# Power.net
KiCad netlist of a schematic drawn in Altium Designer
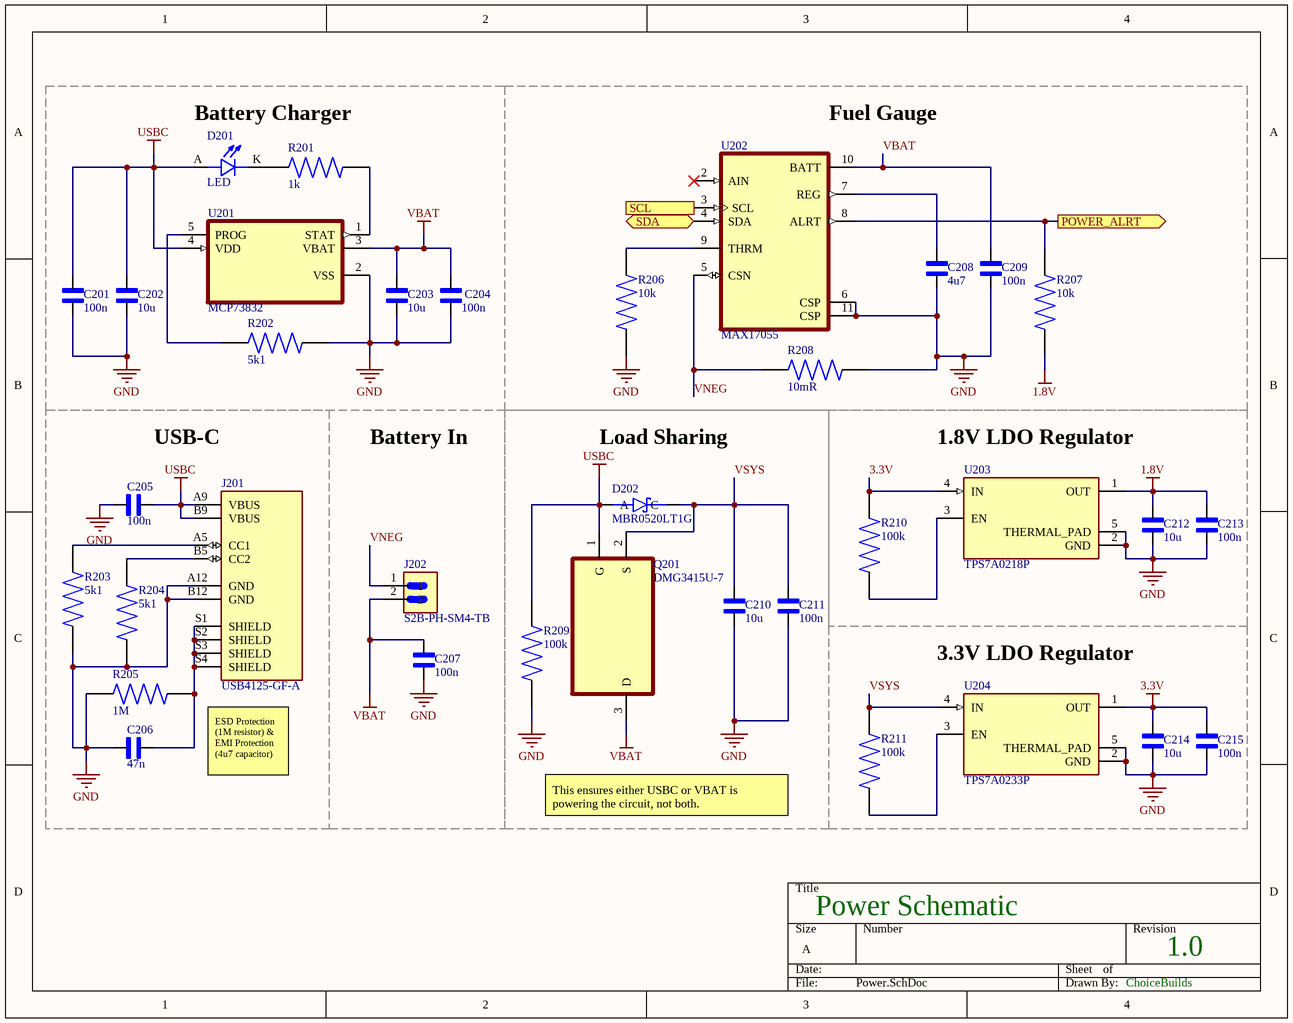
[diagram p0: Power.SchDoc]

(export (version "E")
  (design (tool "Eeschema 10.0.6"))
  (components
    (comp (ref "C201") (value "100n") (footprint "0402c") (libsource (lib "") (part "0402c_1")))
    (comp (ref "C202") (value "10u") (footprint "0603c") (libsource (lib "UbiWatch_SchLib") (part "0603c")))
    (comp (ref "C203") (value "10u") (footprint "0603c") (libsource (lib "") (part "0603c_1")))
    (comp (ref "C204") (value "100n") (footprint "0402c") (libsource (lib "") (part "0402c_1")))
    (comp (ref "C205") (value "100n") (footprint "0402c") (libsource (lib "") (part "0402c_2")))
    (comp (ref "C206") (value "47n") (footprint "0402c") (libsource (lib "") (part "0402c_2")))
    (comp (ref "C207") (value "100n") (footprint "0402c") (libsource (lib "UbiWatch_SchLib") (part "0402c")))
    (comp (ref "C208") (value "4u7") (footprint "0603c") (libsource (lib "UbiWatch_SchLib") (part "0603c")))
    (comp (ref "C209") (value "100n") (footprint "0402c") (libsource (lib "") (part "0402c_1")))
    (comp (ref "C210") (value "10u") (footprint "0603c") (libsource (lib "UbiWatch_SchLib") (part "0603c")))
    (comp (ref "C211") (value "100n") (footprint "0402c") (libsource (lib "") (part "0402c_1")))
    (comp (ref "C212") (value "10u") (footprint "0603c") (libsource (lib "UbiWatch_SchLib") (part "0603c")))
    (comp (ref "C213") (value "100n") (footprint "0402c") (libsource (lib "") (part "0402c_1")))
    (comp (ref "C214") (value "10u") (footprint "0603c") (libsource (lib "UbiWatch_SchLib") (part "0603c")))
    (comp (ref "C215") (value "100n") (footprint "0402c") (libsource (lib "") (part "0402c_1")))
    (comp (ref "D201") (value "LED") (footprint ".LED") (libsource (lib "UbiWatch_SchLib") (part ".LED")))
    (comp (ref "D202")
      (value "MBR0520LT1G")
      (footprint "MBR0520LT1G")
      (libsource (lib "UbiWatch_SchLib") (part "MBR0520LT1G"))
    )
    (comp (ref "J201")
      (value "USB4125-GF-A")
      (footprint "USB4125-GF-A")
      (libsource (lib "JWatch_SchLib") (part "USB4125-GF-A"))
    )
    (comp (ref "J202")
      (value "S2B-PH-SM4-TB")
      (footprint "S2B-PH-SM4-TB")
      (libsource (lib "UbiWatch_SchLib") (part "S2B-PH-SM4-TB"))
    )
    (comp (ref "Q201")
      (value "DMG3415U-7")
      (footprint "DMG3415U-7")
      (libsource (lib "UbiWatch_SchLib") (part "DMG3415U-7"))
    )
    (comp (ref "R201") (value "1k") (footprint "0402r") (libsource (lib "UbiWatch_SchLib") (part "0402r")))
    (comp (ref "R202") (value "5k1") (footprint "0402r") (libsource (lib "UbiWatch_SchLib") (part "0402r")))
    (comp (ref "R203") (value "5k1") (footprint "0402r") (libsource (lib "UbiWatch_SchLib") (part "0402r")))
    (comp (ref "R204") (value "5k1") (footprint "0402r") (libsource (lib "UbiWatch_SchLib") (part "0402r")))
    (comp (ref "R205") (value "1M") (footprint "0402r") (libsource (lib "UbiWatch_SchLib") (part "0402r")))
    (comp (ref "R206") (value "10k") (footprint "0402r") (libsource (lib "UbiWatch_SchLib") (part "0402r")))
    (comp (ref "R207") (value "10k") (footprint "0402r") (libsource (lib "UbiWatch_SchLib") (part "0402r")))
    (comp (ref "R208") (value "10mR") (footprint "0805r") (libsource (lib "UbiWatch_SchLib") (part "0805r")))
    (comp (ref "R209") (value "100k") (footprint "0402r") (libsource (lib "UbiWatch_SchLib") (part "0402r")))
    (comp (ref "R210") (value "100k") (footprint "0402r") (libsource (lib "UbiWatch_SchLib") (part "0402r")))
    (comp (ref "R211") (value "100k") (footprint "0402r") (libsource (lib "UbiWatch_SchLib") (part "0402r")))
    (comp (ref "U201")
      (value "MCP73832")
      (footprint "MCP73832")
      (libsource (lib "JWatch_SchLib") (part "MCP73832"))
    )
    (comp (ref "U202")
      (value "MAX17055")
      (footprint "MAX17055")
      (libsource (lib "JWatch_SchLib") (part "MAX17055"))
    )
    (comp (ref "U203")
      (value "TPS7A0218P")
      (footprint "TPS7A0218P")
      (libsource (lib "JWatch_SchLib") (part "TPS7A0218P"))
    )
    (comp (ref "U204")
      (value "TPS7A0233P")
      (footprint "TPS7A0233P")
      (libsource (lib "JWatch_SchLib") (part "TPS7A0233P"))
    )
  )
  (nets
    (net (code "1") (name "/POWER_ALRT") (class "Default")
      (node (ref "R207") (pin "2") (pinfunction "2_2") (pintype "passive"))
      (node (ref "U202") (pin "8") (pinfunction "ALRT_8") (pintype "output"))
    )
    (net (code "2") (name "/SCL") (class "Default")
      (node (ref "U202") (pin "3") (pinfunction "SCL_3") (pintype "input"))
    )
    (net (code "3") (name "/SDA") (class "Default")
      (node (ref "U202") (pin "4") (pinfunction "SDA_4") (pintype "input"))
    )
    (net (code "4") (name "/VNEG") (class "Default")
      (node (ref "J202") (pin "1") (pinfunction "1_1") (pintype "passive"))
      (node (ref "R208") (pin "1") (pinfunction "1_1") (pintype "passive"))
      (node (ref "U202") (pin "5") (pinfunction "CSN_5") (pintype "bidirectional"))
    )
    (net (code "5") (name "/VSYS") (class "Default")
      (node (ref "C210") (pin "2") (pinfunction "2_2") (pintype "passive"))
      (node (ref "C211") (pin "2") (pinfunction "2_2") (pintype "passive"))
      (node (ref "D202") (pin "C") (pinfunction "C_C") (pintype "passive"))
      (node (ref "Q201") (pin "2") (pinfunction "S_2") (pintype "power_in"))
      (node (ref "R211") (pin "2") (pinfunction "2_2") (pintype "passive"))
      (node (ref "U204") (pin "4") (pinfunction "IN_4") (pintype "input"))
    )
    (net (code "6") (name "1.8V") (class "Default")
      (node (ref "C212") (pin "2") (pinfunction "2_2") (pintype "passive"))
      (node (ref "C213") (pin "2") (pinfunction "2_2") (pintype "passive"))
      (node (ref "R207") (pin "1") (pinfunction "1_1") (pintype "passive"))
      (node (ref "U203") (pin "1") (pinfunction "OUT_1") (pintype "power_in"))
    )
    (net (code "7") (name "3.3V") (class "Default")
      (node (ref "C214") (pin "2") (pinfunction "2_2") (pintype "passive"))
      (node (ref "C215") (pin "2") (pinfunction "2_2") (pintype "passive"))
      (node (ref "R210") (pin "2") (pinfunction "2_2") (pintype "passive"))
      (node (ref "U203") (pin "4") (pinfunction "IN_4") (pintype "input"))
      (node (ref "U204") (pin "1") (pinfunction "OUT_1") (pintype "power_in"))
    )
    (net (code "8") (name "GND") (class "Default")
      (node (ref "C201") (pin "1") (pinfunction "1_1") (pintype "passive"))
      (node (ref "C202") (pin "1") (pinfunction "1_1") (pintype "passive"))
      (node (ref "C203") (pin "1") (pinfunction "1_1") (pintype "passive"))
      (node (ref "C204") (pin "1") (pinfunction "1_1") (pintype "passive"))
      (node (ref "C205") (pin "1") (pinfunction "1_1") (pintype "passive"))
      (node (ref "C206") (pin "1") (pinfunction "1_1") (pintype "passive"))
      (node (ref "C207") (pin "2") (pinfunction "2_2") (pintype "passive"))
      (node (ref "C208") (pin "1") (pinfunction "1_1") (pintype "passive"))
      (node (ref "C209") (pin "1") (pinfunction "1_1") (pintype "passive"))
      (node (ref "C210") (pin "1") (pinfunction "1_1") (pintype "passive"))
      (node (ref "C211") (pin "1") (pinfunction "1_1") (pintype "passive"))
      (node (ref "C212") (pin "1") (pinfunction "1_1") (pintype "passive"))
      (node (ref "C213") (pin "1") (pinfunction "1_1") (pintype "passive"))
      (node (ref "C214") (pin "1") (pinfunction "1_1") (pintype "passive"))
      (node (ref "C215") (pin "1") (pinfunction "1_1") (pintype "passive"))
      (node (ref "J201") (pin "A12") (pinfunction "GND_A12") (pintype "power_in"))
      (node (ref "J201") (pin "B12") (pinfunction "GND_B12") (pintype "power_in"))
      (node (ref "R202") (pin "2") (pinfunction "2_2") (pintype "passive"))
      (node (ref "R203") (pin "1") (pinfunction "1_1") (pintype "passive"))
      (node (ref "R204") (pin "1") (pinfunction "1_1") (pintype "passive"))
      (node (ref "R205") (pin "1") (pinfunction "1_1") (pintype "passive"))
      (node (ref "R206") (pin "1") (pinfunction "1_1") (pintype "passive"))
      (node (ref "R208") (pin "2") (pinfunction "2_2") (pintype "passive"))
      (node (ref "R209") (pin "1") (pinfunction "1_1") (pintype "passive"))
      (node (ref "U201") (pin "2") (pinfunction "VSS_2") (pintype "power_in"))
      (node (ref "U202") (pin "11") (pinfunction "CSP_11") (pintype "power_in"))
      (node (ref "U202") (pin "6") (pinfunction "CSP_6") (pintype "power_in"))
      (node (ref "U203") (pin "2") (pinfunction "GND_2") (pintype "power_in"))
      (node (ref "U203") (pin "5") (pinfunction "THERMAL_PAD_5") (pintype "power_in"))
      (node (ref "U204") (pin "2") (pinfunction "GND_2") (pintype "power_in"))
      (node (ref "U204") (pin "5") (pinfunction "THERMAL_PAD_5") (pintype "power_in"))
    )
    (net (code "9") (name "Net-(C206-Pad2)") (class "Default")
      (node (ref "C206") (pin "2") (pinfunction "2_2") (pintype "passive"))
      (node (ref "J201") (pin "S1") (pinfunction "SHIELD_S1") (pintype "passive"))
      (node (ref "J201") (pin "S2") (pinfunction "SHIELD_S2") (pintype "passive"))
      (node (ref "J201") (pin "S3") (pinfunction "SHIELD_S3") (pintype "passive"))
      (node (ref "J201") (pin "S4") (pinfunction "SHIELD_S4") (pintype "passive"))
      (node (ref "R205") (pin "2") (pinfunction "2_2") (pintype "passive"))
    )
    (net (code "10") (name "Net-(D201-PadK)") (class "Default")
      (node (ref "D201") (pin "K") (pinfunction "K_K") (pintype "passive"))
      (node (ref "R201") (pin "1") (pinfunction "1_1") (pintype "passive"))
    )
    (net (code "11") (name "Net-(J201-CC1)") (class "Default")
      (node (ref "J201") (pin "A5") (pinfunction "CC1_A5") (pintype "bidirectional"))
      (node (ref "R203") (pin "2") (pinfunction "2_2") (pintype "passive"))
    )
    (net (code "12") (name "Net-(J201-CC2)") (class "Default")
      (node (ref "J201") (pin "B5") (pinfunction "CC2_B5") (pintype "bidirectional"))
      (node (ref "R204") (pin "2") (pinfunction "2_2") (pintype "passive"))
    )
    (net (code "13") (name "Net-(U201-PROG)") (class "Default")
      (node (ref "R202") (pin "1") (pinfunction "1_1") (pintype "passive"))
      (node (ref "U201") (pin "5") (pinfunction "PROG_5") (pintype "passive"))
    )
    (net (code "14") (name "Net-(U201-STAT)") (class "Default")
      (node (ref "R201") (pin "2") (pinfunction "2_2") (pintype "passive"))
      (node (ref "U201") (pin "1") (pinfunction "STAT_1") (pintype "output"))
    )
    (net (code "15") (name "Net-(U202-REG)") (class "Default")
      (node (ref "C208") (pin "2") (pinfunction "2_2") (pintype "passive"))
      (node (ref "U202") (pin "7") (pinfunction "REG_7") (pintype "output"))
    )
    (net (code "16") (name "Net-(U202-THRM)") (class "Default")
      (node (ref "R206") (pin "2") (pinfunction "2_2") (pintype "passive"))
      (node (ref "U202") (pin "9") (pinfunction "THRM_9") (pintype "passive"))
    )
    (net (code "17") (name "Net-(U203-EN)") (class "Default")
      (node (ref "R210") (pin "1") (pinfunction "1_1") (pintype "passive"))
      (node (ref "U203") (pin "3") (pinfunction "EN_3") (pintype "passive"))
    )
    (net (code "18") (name "Net-(U204-EN)") (class "Default")
      (node (ref "R211") (pin "1") (pinfunction "1_1") (pintype "passive"))
      (node (ref "U204") (pin "3") (pinfunction "EN_3") (pintype "passive"))
    )
    (net (code "19") (name "USBC") (class "Default")
      (node (ref "C201") (pin "2") (pinfunction "2_2") (pintype "passive"))
      (node (ref "C202") (pin "2") (pinfunction "2_2") (pintype "passive"))
      (node (ref "C205") (pin "2") (pinfunction "2_2") (pintype "passive"))
      (node (ref "D201") (pin "A") (pinfunction "A_A") (pintype "passive"))
      (node (ref "D202") (pin "A") (pinfunction "A_A") (pintype "passive"))
      (node (ref "J201") (pin "A9") (pinfunction "VBUS_A9") (pintype "power_in"))
      (node (ref "J201") (pin "B9") (pinfunction "VBUS_B9") (pintype "power_in"))
      (node (ref "Q201") (pin "1") (pinfunction "G_1") (pintype "power_in"))
      (node (ref "R209") (pin "2") (pinfunction "2_2") (pintype "passive"))
      (node (ref "U201") (pin "4") (pinfunction "VDD_4") (pintype "input"))
    )
    (net (code "20") (name "VBAT") (class "Default")
      (node (ref "C203") (pin "2") (pinfunction "2_2") (pintype "passive"))
      (node (ref "C204") (pin "2") (pinfunction "2_2") (pintype "passive"))
      (node (ref "C207") (pin "1") (pinfunction "1_1") (pintype "passive"))
      (node (ref "C209") (pin "2") (pinfunction "2_2") (pintype "passive"))
      (node (ref "J202") (pin "2") (pinfunction "2_2") (pintype "passive"))
      (node (ref "Q201") (pin "3") (pinfunction "D_3") (pintype "power_in"))
      (node (ref "U201") (pin "3") (pinfunction "VBAT_3") (pintype "power_in"))
      (node (ref "U202") (pin "10") (pinfunction "BATT_10") (pintype "power_in"))
    )
    (net (code "21") (name "unconnected-(U202-AIN-Pad2)") (class "Default")
      (node (ref "U202") (pin "2") (pinfunction "AIN_2") (pintype "input+no_connect"))
    )
  )
)
